# frm-voltrod.net
KiCad netlist of a schematic drawn in Altium Designer
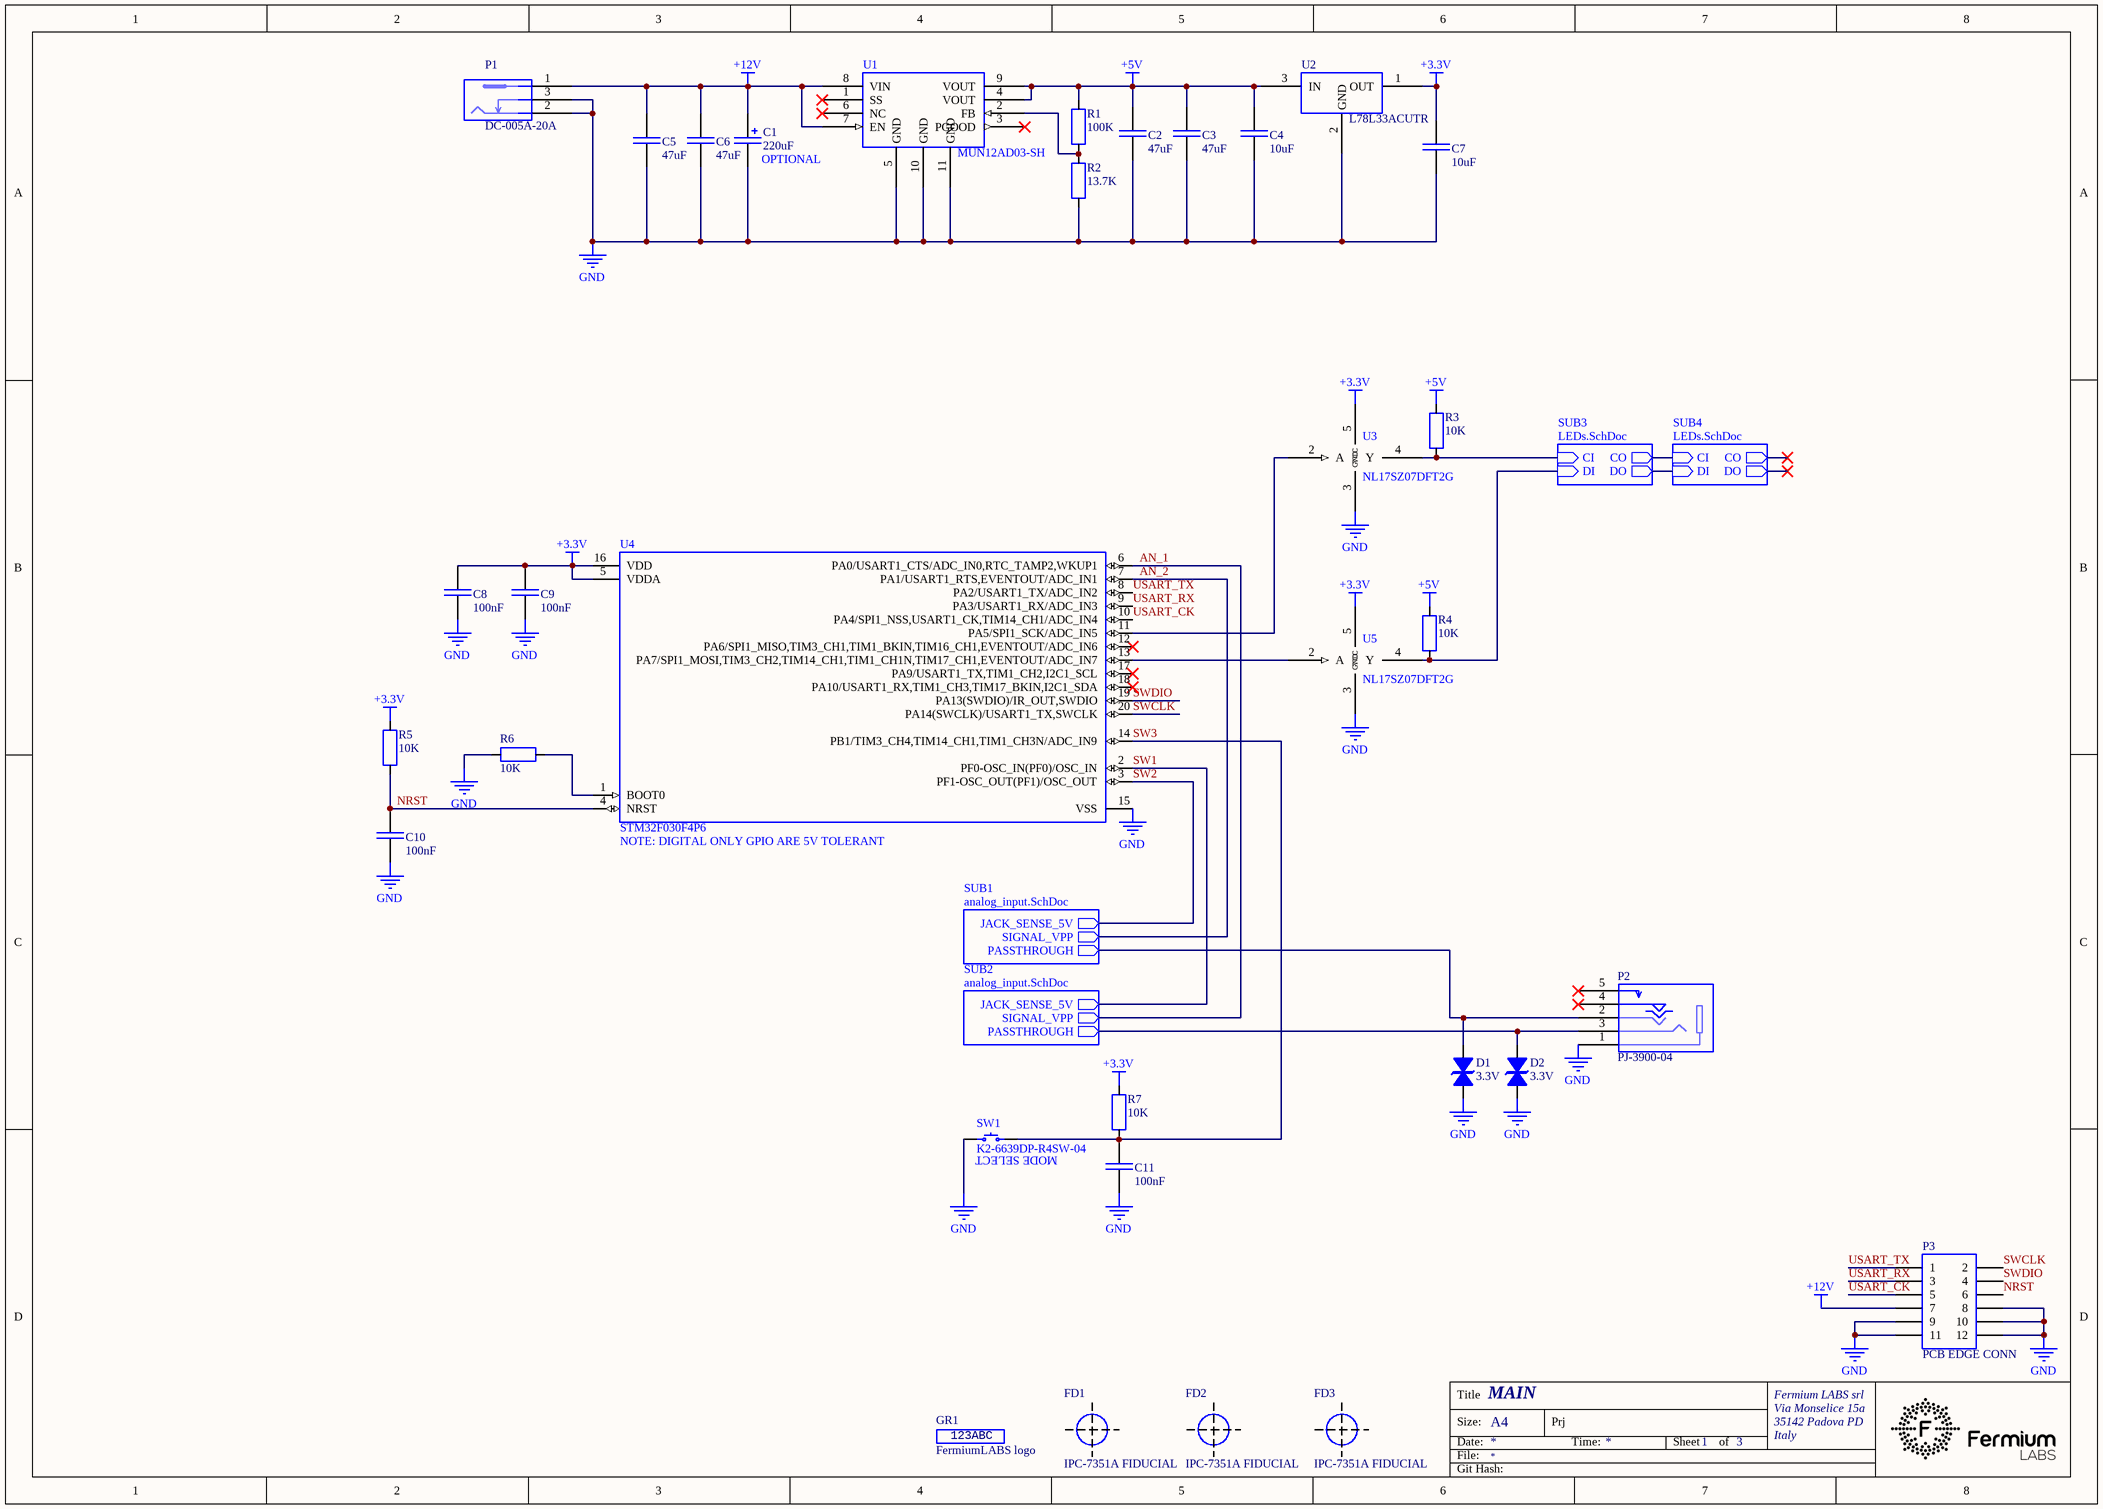
[diagram p0: frm-voltrod.SchDoc]

(export (version "E")
  (design (tool "Eeschema 10.0.6"))
  (components
    (comp (ref "C1")
      (value "220uF")
      (footprint "3924B366-8672-45E9-B0BE-62DACC24E783")
      (description "CAP  THT ELEC 220uF 25V 20%")
      (fields (field (name "PART NUMBER") "1a28df19-6d3e-4a71-836c-f22920f8e8ab"))
      (libsource (lib "frmdblib") (part "GENERIC_C_ELEC"))
    )
    (comp (ref "C2")
      (value "47uF")
      (footprint "CAP 0805_2012")
      (description "CAP SMD MLCC 47uF 6.3V 0805 X5R")
      (fields (field (name "PART NUMBER") "7e40707e-5198-472b-97ae-d9f3cd497999"))
      (libsource (lib "frmdblib") (part "GENERIC_C"))
    )
    (comp (ref "C3")
      (value "47uF")
      (footprint "CAP 0805_2012")
      (description "CAP SMD MLCC 47uF 6.3V 0805 X5R")
      (fields (field (name "PART NUMBER") "7e40707e-5198-472b-97ae-d9f3cd497999"))
      (libsource (lib "frmdblib") (part "GENERIC_C"))
    )
    (comp (ref "C4")
      (value "10uF")
      (footprint "CAP 0805_2012")
      (description "CAP SMD MLCC 10uF 25V 0805 X5R")
      (fields (field (name "PART NUMBER") "1ffbe5a9-0884-4740-bdad-20a6a98400e6"))
      (libsource (lib "frmdblib") (part "GENERIC_C"))
    )
    (comp (ref "C5")
      (value "47uF")
      (footprint "CAP 0805_2012")
      (description "CAP SMD MLCC 47uF 6.3V 0805 X5R")
      (fields (field (name "PART NUMBER") "7e40707e-5198-472b-97ae-d9f3cd497999"))
      (libsource (lib "frmdblib") (part "GENERIC_C"))
    )
    (comp (ref "C6")
      (value "47uF")
      (footprint "CAP 0805_2012")
      (description "CAP SMD MLCC 47uF 6.3V 0805 X5R")
      (fields (field (name "PART NUMBER") "7e40707e-5198-472b-97ae-d9f3cd497999"))
      (libsource (lib "frmdblib") (part "GENERIC_C"))
    )
    (comp (ref "C7")
      (value "10uF")
      (footprint "CAP 0805_2012")
      (description "CAP SMD MLCC 10uF 25V 0805 X5R")
      (fields (field (name "PART NUMBER") "1ffbe5a9-0884-4740-bdad-20a6a98400e6"))
      (libsource (lib "frmdblib") (part "GENERIC_C"))
    )
    (comp (ref "C8")
      (value "100nF")
      (footprint "CAP 0603_1608")
      (description "CAP SMD MLCC 100nF 25V 0603 X7R")
      (fields (field (name "PART NUMBER") "02841f84-ac15-41b5-9e17-915f8f067828"))
      (libsource (lib "frmdblib") (part "GENERIC_C"))
    )
    (comp (ref "C9")
      (value "100nF")
      (footprint "CAP 0603_1608")
      (description "CAP SMD MLCC 100nF 25V 0603 X7R")
      (fields (field (name "PART NUMBER") "02841f84-ac15-41b5-9e17-915f8f067828"))
      (libsource (lib "frmdblib") (part "GENERIC_C"))
    )
    (comp (ref "C10")
      (value "100nF")
      (footprint "CAP 0603_1608")
      (description "CAP SMD MLCC 100nF 25V 0603 X7R")
      (fields (field (name "PART NUMBER") "02841f84-ac15-41b5-9e17-915f8f067828"))
      (libsource (lib "frmdblib") (part "GENERIC_C"))
    )
    (comp (ref "C11")
      (value "100nF")
      (footprint "CAP 0603_1608")
      (description "CAP SMD MLCC 100nF 25V 0603 X7R")
      (fields (field (name "PART NUMBER") "02841f84-ac15-41b5-9e17-915f8f067828"))
      (libsource (lib "frmdblib") (part "GENERIC_C"))
    )
    (comp (ref "D1")
      (value "3.3V")
      (footprint "SOD523F")
      (description "DIODE SMD TVS 3.3V BIDIRECTIONAL SOD-523")
      (fields (field (name "PART NUMBER") "d6266fd0-7428-4fb9-a062-338cdce926fd"))
      (libsource (lib "frmdblib") (part "GENERIC_D_TVS_BI"))
    )
    (comp (ref "D2")
      (value "3.3V")
      (footprint "SOD523F")
      (description "DIODE SMD TVS 3.3V BIDIRECTIONAL SOD-523")
      (fields (field (name "PART NUMBER") "d6266fd0-7428-4fb9-a062-338cdce926fd"))
      (libsource (lib "frmdblib") (part "GENERIC_D_TVS_BI"))
    )
    (comp (ref "FD1")
      (value "IPC-7351A FIDUCIAL")
      (footprint "FIDUCIAL-IPC-7351A")
      (description "GRAPHICS FIDUCIAL IPC-7351A")
      (fields (field (name "PART NUMBER") "19da4612-eb95-43bb-9984-553a52b2a224"))
      (libsource (lib "frmdblib") (part "GENERIC_FIDUCIAL"))
    )
    (comp (ref "FD2")
      (value "IPC-7351A FIDUCIAL")
      (footprint "FIDUCIAL-IPC-7351A")
      (description "GRAPHICS FIDUCIAL IPC-7351A")
      (fields (field (name "PART NUMBER") "19da4612-eb95-43bb-9984-553a52b2a224"))
      (libsource (lib "frmdblib") (part "GENERIC_FIDUCIAL"))
    )
    (comp (ref "FD3")
      (value "IPC-7351A FIDUCIAL")
      (footprint "FIDUCIAL-IPC-7351A")
      (description "GRAPHICS FIDUCIAL IPC-7351A")
      (fields (field (name "PART NUMBER") "19da4612-eb95-43bb-9984-553a52b2a224"))
      (libsource (lib "frmdblib") (part "GENERIC_FIDUCIAL"))
    )
    (comp (ref "GR1")
      (value "FermiumLABS logo")
      (footprint "5394DE47-A0E8-4329-8464-7791B7C19310")
      (description "GRAPHICS LOGO FERMIUM LABS SRL")
      (fields (field (name "PART NUMBER") "50f8ea88-0034-49fe-a263-d8e97bc35e2f"))
      (libsource (lib "frmdblib") (part "GENERIC_GRAPHIC"))
    )
    (comp (ref "P1")
      (value "DC-005A-20A")
      (footprint "F0972D8A-C5C0-4A84-836D-A9666EE65C2D")
      (description "CONN THT DC JACK 0.5A 30VDC 5Kcycles")
      (fields (field (name "PART NUMBER") "b53db51a-1725-412b-9039-fa7a45c7c438"))
      (libsource (lib "frmdblib") (part "34A1CD0B-E262-46EF-B9F1-39CB809C308F"))
    )
    (comp (ref "P2")
      (value "PJ-3900-04")
      (footprint "7EF2B92C-0FC9-4C85-B662-5CEC65BFCCC4")
      (description "CONN THT 3.5mm AUDIO STEREO AUX SWITCH")
      (fields (field (name "PART NUMBER") "80507a24-5d7c-4cf5-953e-f54832d54564"))
      (libsource (lib "frmdblib") (part "46E41D2F-79BD-46AC-B778-70B2D50A946A"))
    )
    (comp (ref "P3")
      (value "PCB EDGE CONN")
      (description "CONN EDGE MALE PCB BRAKE-AWAY 6X2")
      (fields (field (name "PART NUMBER") "54ab5b9b-caf0-4ef6-9923-0d5cbea9903e"))
      (libsource (lib "frmdblib") (part "Header 6X2"))
    )
    (comp (ref "R1")
      (value "100K")
      (footprint "RES 0603_1608")
      (description "RES SMD 100K OHM 1% 1/10W 0603")
      (fields (field (name "PART NUMBER") "76af10b3-9d85-4b5c-a2d6-26cc74f432f7"))
      (libsource (lib "frmdblib") (part "GENERIC_R"))
    )
    (comp (ref "R2")
      (value "13.7K")
      (footprint "RES 0603_1608")
      (description "RES SMD 13.7K OHM 1% 1/10W 0603")
      (fields (field (name "PART NUMBER") "781a7ab4-3e94-4acf-a8dd-6c7705842145"))
      (libsource (lib "frmdblib") (part "GENERIC_R"))
    )
    (comp (ref "R3")
      (value "10K")
      (footprint "RES 0603_1608")
      (description "RES SMD 10K OHM 1% 1/10W 0603")
      (fields (field (name "PART NUMBER") "93242766-ba1d-462d-b58f-ce1dfc4129c8"))
      (libsource (lib "frmdblib") (part "GENERIC_R"))
    )
    (comp (ref "R4")
      (value "10K")
      (footprint "RES 0603_1608")
      (description "RES SMD 10K OHM 1% 1/10W 0603")
      (fields (field (name "PART NUMBER") "93242766-ba1d-462d-b58f-ce1dfc4129c8"))
      (libsource (lib "frmdblib") (part "GENERIC_R"))
    )
    (comp (ref "R5")
      (value "10K")
      (footprint "RES 0603_1608")
      (description "RES SMD 10K OHM 1% 1/10W 0603")
      (fields (field (name "PART NUMBER") "93242766-ba1d-462d-b58f-ce1dfc4129c8"))
      (libsource (lib "frmdblib") (part "GENERIC_R"))
    )
    (comp (ref "R6")
      (value "10K")
      (footprint "RES 0603_1608")
      (description "RES SMD 10K OHM 1% 1/10W 0603")
      (fields (field (name "PART NUMBER") "93242766-ba1d-462d-b58f-ce1dfc4129c8"))
      (libsource (lib "frmdblib") (part "GENERIC_R"))
    )
    (comp (ref "R7")
      (value "10K")
      (footprint "RES 0603_1608")
      (description "RES SMD 10K OHM 1% 1/10W 0603")
      (fields (field (name "PART NUMBER") "93242766-ba1d-462d-b58f-ce1dfc4129c8"))
      (libsource (lib "frmdblib") (part "GENERIC_R"))
    )
    (comp (ref "SW1")
      (value "K2-6639DP-R4SW-04")
      (footprint "F856BBF7-B441-4D4F-94A5-26E8A4FA0FB8")
      (description "SWITCH SPST-NO TACT 6X6mm h12mm")
      (fields (field (name "PART NUMBER") "403559d4-003c-4544-9ba1-5f60eb47cd4e"))
      (libsource (lib "frmdblib") (part "GENERIC_SWITCH_SPST_NO"))
    )
    (comp (ref "U1")
      (value "MUN12AD03-SH")
      (footprint "2886F06F-953A-4A60-956C-DE72111049AF")
      (description "IC DC-DC MODULE REG  4.5-16Vin  0.6-5.0Vout 3A 91%")
      (fields (field (name "PART NUMBER") "bc00cdda-655c-4312-be5e-62c0cd6c1179"))
      (libsource (lib "frmdblib") (part "20948790-CFFE-4D9D-84D2-9DD22F37FBF3"))
    )
    (comp (ref "U2")
      (value "L78L33ACUTR")
      (footprint "E733EFB9-FE91-4AE9-9197-29251971C3DC")
      (description "IC SMD LINEAR VOLTAGE REGULATOR 3.3V 100mA SOT-89")
      (fields (field (name "PART NUMBER") "8cc975d7-ef9f-4621-a9d5-14e4ba8cc85a"))
      (libsource (lib "frmdblib") (part "FCB39772-D6AF-4D61-BC58-A46A50428B6B"))
    )
    (comp (ref "U3")
      (value "NL17SZ07DFT2G")
      (footprint "9DE955BE-AB92-4157-9666-3C064124D2CC")
      (description "IC SMD BUFFER NON-INVERTING OPEN-DRAIN SOT-353")
      (fields (field (name "PART NUMBER") "a3d656f3-fbd6-4576-b355-9fd6caec7ecf"))
      (libsource (lib "frmdblib") (part "18F95C72-C400-4D65-959A-AA806554FB53"))
    )
    (comp (ref "U4")
      (value "STM32F030F4P6")
      (footprint "206192DB-2106-4C81-8503-66D7D3BDF6B3")
      (description "IC SMD MICROCONTROLLER STM32F030F4P6 16KB 4KB TSSOP-20")
      (fields (field (name "PART NUMBER") "6654dce5-3670-4880-9fa3-4487e523ee9f"))
      (libsource (lib "frmdblib") (part "69ECCCB1-AD06-4B70-932A-5AD00B4B1497"))
    )
    (comp (ref "U5")
      (value "NL17SZ07DFT2G")
      (footprint "9DE955BE-AB92-4157-9666-3C064124D2CC")
      (description "IC SMD BUFFER NON-INVERTING OPEN-DRAIN SOT-353")
      (fields (field (name "PART NUMBER") "a3d656f3-fbd6-4576-b355-9fd6caec7ecf"))
      (libsource (lib "frmdblib") (part "18F95C72-C400-4D65-959A-AA806554FB53"))
    )
  )
  (nets
    (net (code "1") (name "+3.3V") (class "Default")
      (node (ref "C7") (pin "2") (pintype "passive"))
      (node (ref "C8") (pin "2") (pintype "passive"))
      (node (ref "C9") (pin "2") (pintype "passive"))
      (node (ref "R5") (pin "2") (pintype "passive"))
      (node (ref "R7") (pin "2") (pintype "passive"))
      (node (ref "U2") (pin "1") (pinfunction "OUT_1") (pintype "passive"))
      (node (ref "U3") (pin "5") (pinfunction "VCC_5") (pintype "passive"))
      (node (ref "U4") (pin "16") (pinfunction "VDD_16") (pintype "power_in"))
      (node (ref "U4") (pin "5") (pinfunction "VDDA_5") (pintype "power_in"))
      (node (ref "U5") (pin "5") (pinfunction "VCC_5") (pintype "passive"))
    )
    (net (code "2") (name "+5V") (class "Default")
      (node (ref "C2") (pin "1") (pintype "passive"))
      (node (ref "C3") (pin "1") (pintype "passive"))
      (node (ref "C4") (pin "2") (pintype "passive"))
      (node (ref "R1") (pin "2") (pintype "passive"))
      (node (ref "R3") (pin "2") (pintype "passive"))
      (node (ref "R4") (pin "2") (pintype "passive"))
      (node (ref "U1") (pin "4") (pinfunction "VOUT_4") (pintype "power_in"))
      (node (ref "U1") (pin "9") (pinfunction "VOUT_9") (pintype "power_in"))
      (node (ref "U2") (pin "3") (pinfunction "IN_3") (pintype "passive"))
    )
    (net (code "3") (name "+12V") (class "Default")
      (node (ref "C1") (pin "1") (pintype "passive"))
      (node (ref "C5") (pin "1") (pintype "passive"))
      (node (ref "C6") (pin "1") (pintype "passive"))
      (node (ref "P1") (pin "1") (pinfunction "1_1") (pintype "passive"))
      (node (ref "P3") (pin "7") (pinfunction "7_7") (pintype "passive"))
      (node (ref "U1") (pin "7") (pinfunction "EN_7") (pintype "input"))
      (node (ref "U1") (pin "8") (pinfunction "VIN_8") (pintype "power_in"))
    )
    (net (code "4") (name "/AN_1") (class "Default")
      (node (ref "U4") (pin "6") (pinfunction "PA0/USART1_CTS/ADC_IN0,RTC_TAMP2,WKUP1_6") (pintype "bidirectional"))
    )
    (net (code "5") (name "/AN_2") (class "Default")
      (node (ref "U4") (pin "7") (pinfunction "PA1/USART1_RTS,EVENTOUT/ADC_IN1_7") (pintype "bidirectional"))
    )
    (net (code "6") (name "/CI") (class "Default")
      (node (ref "R3") (pin "1") (pintype "passive"))
      (node (ref "U3") (pin "4") (pinfunction "Y_4") (pintype "open_collector"))
    )
    (net (code "9") (name "/DI") (class "Default")
      (node (ref "R4") (pin "1") (pintype "passive"))
      (node (ref "U5") (pin "4") (pinfunction "Y_4") (pintype "open_collector"))
    )
    (net (code "12") (name "/NRST") (class "Default")
      (node (ref "C10") (pin "2") (pintype "passive"))
      (node (ref "P3") (pin "6") (pinfunction "6_6") (pintype "passive"))
      (node (ref "R5") (pin "1") (pintype "passive"))
      (node (ref "U4") (pin "4") (pinfunction "NRST_4") (pintype "bidirectional"))
    )
    (net (code "13") (name "/PASSTHROUGH") (class "Default")
      (node (ref "D2") (pin "1") (pintype "passive"))
      (node (ref "P2") (pin "3") (pinfunction "L_3") (pintype "passive"))
    )
    (net (code "14") (name "/PASSTHROUGH_1") (class "Default")
      (node (ref "D1") (pin "1") (pintype "passive"))
      (node (ref "P2") (pin "2") (pinfunction "R_2") (pintype "passive"))
    )
    (net (code "15") (name "/SW1") (class "Default")
      (node (ref "U4") (pin "2") (pinfunction "PF0-OSC_IN(PF0)/OSC_IN_2") (pintype "bidirectional"))
    )
    (net (code "16") (name "/SW2") (class "Default")
      (node (ref "U4") (pin "3") (pinfunction "PF1-OSC_OUT(PF1)/OSC_OUT_3") (pintype "bidirectional"))
    )
    (net (code "17") (name "/SW3") (class "Default")
      (node (ref "C11") (pin "2") (pintype "passive"))
      (node (ref "R7") (pin "1") (pintype "passive"))
      (node (ref "SW1") (pin "2") (pinfunction "2_2") (pintype "passive"))
      (node (ref "U4") (pin "14") (pinfunction "PB1/TIM3_CH4,TIM14_CH1,TIM1_CH3N/ADC_IN9_14") (pintype "bidirectional"))
    )
    (net (code "18") (name "/SWCLK") (class "Default")
      (node (ref "P3") (pin "2") (pinfunction "2_2") (pintype "passive"))
      (node (ref "U4") (pin "20") (pinfunction "PA14(SWCLK)/USART1_TX,SWCLK_20") (pintype "bidirectional"))
    )
    (net (code "19") (name "/SWDIO") (class "Default")
      (node (ref "P3") (pin "4") (pinfunction "4_4") (pintype "passive"))
      (node (ref "U4") (pin "19") (pinfunction "PA13(SWDIO)/IR_OUT,SWDIO_19") (pintype "bidirectional"))
    )
    (net (code "20") (name "/USART_CK") (class "Default")
      (node (ref "P3") (pin "5") (pinfunction "5_5") (pintype "passive"))
      (node (ref "U4") (pin "10") (pinfunction "PA4/SPI1_NSS,USART1_CK,TIM14_CH1/ADC_IN4_10") (pintype "bidirectional"))
    )
    (net (code "21") (name "/USART_RX") (class "Default")
      (node (ref "P3") (pin "3") (pinfunction "3_3") (pintype "passive"))
      (node (ref "U4") (pin "9") (pinfunction "PA3/USART1_RX/ADC_IN3_9") (pintype "bidirectional"))
    )
    (net (code "22") (name "/USART_TX") (class "Default")
      (node (ref "P3") (pin "1") (pinfunction "1_1") (pintype "passive"))
      (node (ref "U4") (pin "8") (pinfunction "PA2/USART1_TX/ADC_IN2_8") (pintype "bidirectional"))
    )
    (net (code "23") (name "GND") (class "Default")
      (node (ref "C1") (pin "2") (pintype "passive"))
      (node (ref "C10") (pin "1") (pintype "passive"))
      (node (ref "C11") (pin "1") (pintype "passive"))
      (node (ref "C2") (pin "2") (pintype "passive"))
      (node (ref "C3") (pin "2") (pintype "passive"))
      (node (ref "C4") (pin "1") (pintype "passive"))
      (node (ref "C5") (pin "2") (pintype "passive"))
      (node (ref "C6") (pin "2") (pintype "passive"))
      (node (ref "C7") (pin "1") (pintype "passive"))
      (node (ref "C8") (pin "1") (pintype "passive"))
      (node (ref "C9") (pin "1") (pintype "passive"))
      (node (ref "D1") (pin "2") (pintype "passive"))
      (node (ref "D2") (pin "2") (pintype "passive"))
      (node (ref "P1") (pin "2") (pinfunction "2_2") (pintype "passive"))
      (node (ref "P1") (pin "3") (pinfunction "3_3") (pintype "passive"))
      (node (ref "P2") (pin "1") (pinfunction "GND_1") (pintype "passive"))
      (node (ref "P3") (pin "10") (pinfunction "10_10") (pintype "passive"))
      (node (ref "P3") (pin "11") (pinfunction "11_11") (pintype "passive"))
      (node (ref "P3") (pin "12") (pinfunction "12_12") (pintype "passive"))
      (node (ref "P3") (pin "8") (pinfunction "8_8") (pintype "passive"))
      (node (ref "P3") (pin "9") (pinfunction "9_9") (pintype "passive"))
      (node (ref "R2") (pin "1") (pintype "passive"))
      (node (ref "R6") (pin "2") (pintype "passive"))
      (node (ref "SW1") (pin "1") (pinfunction "1_1") (pintype "passive"))
      (node (ref "U1") (pin "10") (pinfunction "GND_10") (pintype "power_in"))
      (node (ref "U1") (pin "11") (pinfunction "GND_11") (pintype "power_in"))
      (node (ref "U1") (pin "5") (pinfunction "GND_5") (pintype "power_in"))
      (node (ref "U2") (pin "2") (pinfunction "GND_2") (pintype "passive"))
      (node (ref "U3") (pin "3") (pinfunction "GND_3") (pintype "power_in"))
      (node (ref "U4") (pin "15") (pinfunction "VSS_15") (pintype "power_in"))
      (node (ref "U5") (pin "3") (pinfunction "GND_3") (pintype "power_in"))
    )
    (net (code "24") (name "Net-(U1-FB)") (class "Default")
      (node (ref "R1") (pin "1") (pintype "passive"))
      (node (ref "R2") (pin "2") (pintype "passive"))
      (node (ref "U1") (pin "2") (pinfunction "FB_2") (pintype "input"))
    )
    (net (code "25") (name "Net-(U3-A)") (class "Default")
      (node (ref "U3") (pin "2") (pinfunction "A_2") (pintype "input"))
      (node (ref "U4") (pin "11") (pinfunction "PA5/SPI1_SCK/ADC_IN5_11") (pintype "bidirectional"))
    )
    (net (code "26") (name "Net-(U4-BOOT0)") (class "Default")
      (node (ref "R6") (pin "1") (pintype "passive"))
      (node (ref "U4") (pin "1") (pinfunction "BOOT0_1") (pintype "input"))
    )
    (net (code "27") (name "Net-(U4-PA7{slash}SPI1_MOSI,TIM3_CH2,TIM14_CH1,TIM1_CH1N,TIM17_CH1,EVENTOUT{slash}ADC_IN7)") (class "Default")
      (node (ref "U4") (pin "13") (pinfunction "PA7/SPI1_MOSI,TIM3_CH2,TIM14_CH1,TIM1_CH1N,TIM17_CH1,EVENTOUT/ADC_IN7_13") (pintype "bidirectional"))
      (node (ref "U5") (pin "2") (pinfunction "A_2") (pintype "input"))
    )
    (net (code "28") (name "unconnected-(P2-AUX-Pad4)") (class "Default")
      (node (ref "P2") (pin "4") (pinfunction "AUX_4") (pintype "passive+no_connect"))
    )
    (net (code "29") (name "unconnected-(P2-AUX-Pad5)") (class "Default")
      (node (ref "P2") (pin "5") (pinfunction "AUX_5") (pintype "passive+no_connect"))
    )
    (net (code "30") (name "unconnected-(U1-NC-Pad6)") (class "Default")
      (node (ref "U1") (pin "6") (pinfunction "NC_6") (pintype "passive+no_connect"))
    )
    (net (code "31") (name "unconnected-(U1-PGOOD-Pad3)") (class "Default")
      (node (ref "U1") (pin "3") (pinfunction "PGOOD_3") (pintype "output+no_connect"))
    )
    (net (code "32") (name "unconnected-(U1-SS-Pad1)") (class "Default")
      (node (ref "U1") (pin "1") (pinfunction "SS_1") (pintype "passive+no_connect"))
    )
    (net (code "33") (name "unconnected-(U4-PA6{slash}SPI1_MISO,TIM3_CH1,TIM1_BKIN,TIM16_CH1,EVENTOUT{slash}ADC_IN6-Pad12)") (class "Default")
      (node (ref "U4") (pin "12") (pinfunction "PA6/SPI1_MISO,TIM3_CH1,TIM1_BKIN,TIM16_CH1,EVENTOUT/ADC_IN6_12") (pintype "bidirectional+no_connect"))
    )
    (net (code "34") (name "unconnected-(U4-PA9{slash}USART1_TX,TIM1_CH2,I2C1_SCL-Pad17)") (class "Default")
      (node (ref "U4") (pin "17") (pinfunction "PA9/USART1_TX,TIM1_CH2,I2C1_SCL_17") (pintype "bidirectional+no_connect"))
    )
    (net (code "35") (name "unconnected-(U4-PA10{slash}USART1_RX,TIM1_CH3,TIM17_BKIN,I2C1_SDA-Pad18)") (class "Default")
      (node (ref "U4") (pin "18") (pinfunction "PA10/USART1_RX,TIM1_CH3,TIM17_BKIN,I2C1_SDA_18") (pintype "bidirectional+no_connect"))
    )
  )
)
